# DronePwrCut.net
KiCad netlist of a schematic drawn in EAGLE
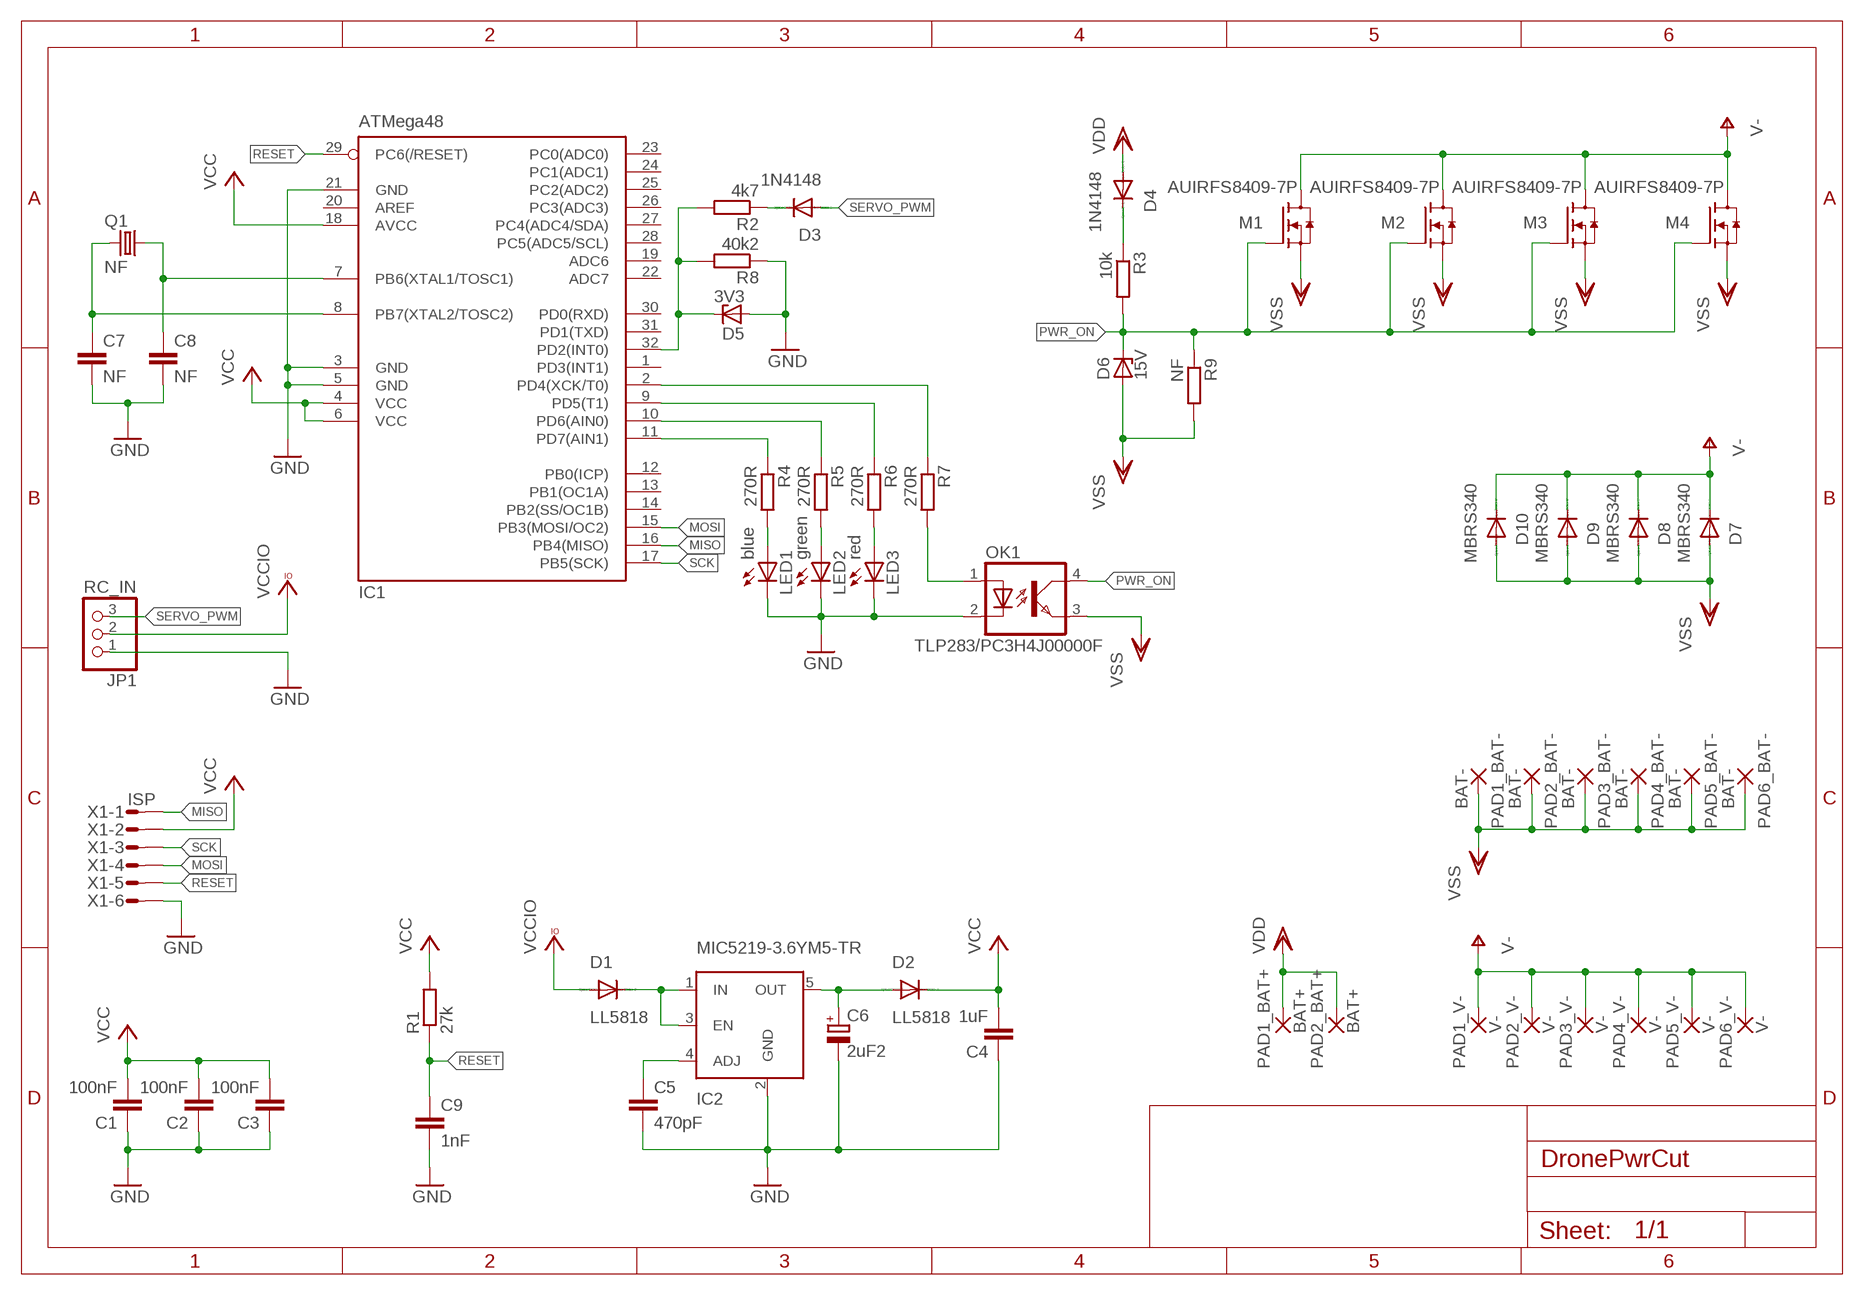
[diagram p0: schematic, sheet 1]

(export (version "E")
  (design (tool "Eeschema 10.0.6"))
  (components
    (comp (ref "C1")
      (value "100nF")
      (footprint "eagle-import:C1206K")
      (libsource (lib "eagle-import") (part "C-EUC1206K"))
    )
    (comp (ref "C2")
      (value "100nF")
      (footprint "eagle-import:C1206K")
      (libsource (lib "eagle-import") (part "C-EUC1206K"))
    )
    (comp (ref "C3")
      (value "100nF")
      (footprint "eagle-import:C1206K")
      (libsource (lib "eagle-import") (part "C-EUC1206K"))
    )
    (comp (ref "C4")
      (value "1uF")
      (footprint "eagle-import:C1206K")
      (libsource (lib "eagle-import") (part "C-EUC1206K"))
    )
    (comp (ref "C5")
      (value "470pF")
      (footprint "eagle-import:C1206K")
      (libsource (lib "eagle-import") (part "C-EUC1206K"))
    )
    (comp (ref "C6")
      (value "2uF2")
      (footprint "eagle-import:SMC_B")
      (libsource (lib "eagle-import") (part "CPOL-EUSMCB"))
    )
    (comp (ref "C7")
      (value "NF")
      (footprint "eagle-import:C1206K")
      (libsource (lib "eagle-import") (part "C-EUC1206K"))
    )
    (comp (ref "C8")
      (value "NF")
      (footprint "eagle-import:C1206K")
      (libsource (lib "eagle-import") (part "C-EUC1206K"))
    )
    (comp (ref "C9")
      (value "1nF")
      (footprint "eagle-import:C1206K")
      (libsource (lib "eagle-import") (part "C-EUC1206K"))
    )
    (comp (ref "D1")
      (value "LL5818")
      (footprint "eagle-import:MELF-MLL41")
      (libsource (lib "eagle-import") (part "DIODE-MELF-MLL41"))
    )
    (comp (ref "D2")
      (value "LL5818")
      (footprint "eagle-import:MELF-MLL41")
      (libsource (lib "eagle-import") (part "DIODE-MELF-MLL41"))
    )
    (comp (ref "D3")
      (value "1N4148")
      (footprint "eagle-import:SOD80C")
      (libsource (lib "eagle-import") (part "DIODE-SOD80C"))
    )
    (comp (ref "D4")
      (value "1N4148")
      (footprint "eagle-import:SOD80C")
      (libsource (lib "eagle-import") (part "DIODE-SOD80C"))
    )
    (comp (ref "D5")
      (value "3V3")
      (footprint "eagle-import:SOD80C")
      (libsource (lib "eagle-import") (part "ZENER-DIODESOD80C"))
    )
    (comp (ref "D6")
      (value "15V")
      (footprint "eagle-import:SOD80C")
      (libsource (lib "eagle-import") (part "ZENER-DIODESOD80C"))
    )
    (comp (ref "D7")
      (value "MBRS340")
      (footprint "eagle-import:SMC")
      (libsource (lib "eagle-import") (part "DIODE-SMC"))
    )
    (comp (ref "D8")
      (value "MBRS340")
      (footprint "eagle-import:SMC")
      (libsource (lib "eagle-import") (part "DIODE-SMC"))
    )
    (comp (ref "D9")
      (value "MBRS340")
      (footprint "eagle-import:SMC")
      (libsource (lib "eagle-import") (part "DIODE-SMC"))
    )
    (comp (ref "D10")
      (value "MBRS340")
      (footprint "eagle-import:SMC")
      (libsource (lib "eagle-import") (part "DIODE-SMC"))
    )
    (comp (ref "IC1")
      (value "ATMega48")
      (footprint "eagle-import:TQFP32-08")
      (fields (field (name "MPN") "ATMEGA8-16AU"))
      (libsource (lib "eagle-import") (part "MEGA8-AI"))
    )
    (comp (ref "IC2")
      (value "MIC5219-3.6YM5-TR")
      (footprint "eagle-import:SOT23-5")
      (fields (field (name "MF") "ALTERA CORPORATION") (field (name "MPN") "MIC5219BM5 TR"))
      (libsource (lib "eagle-import") (part "MIC5219BM5"))
    )
    (comp (ref "JP1")
      (value "RC_IN")
      (footprint "eagle-import:1X03")
      (libsource (lib "eagle-import") (part "PINHD-1X3"))
    )
    (comp (ref "LED1")
      (value "blue")
      (footprint "eagle-import:CHIPLED_1206")
      (libsource (lib "eagle-import") (part "LEDCHIPLED_1206"))
    )
    (comp (ref "LED2")
      (value "green")
      (footprint "eagle-import:CHIPLED_1206")
      (libsource (lib "eagle-import") (part "LEDCHIPLED_1206"))
    )
    (comp (ref "LED3")
      (value "red")
      (footprint "eagle-import:CHIPLED_1206")
      (libsource (lib "eagle-import") (part "LEDCHIPLED_1206"))
    )
    (comp (ref "M1")
      (value "AUIRFS8409-7P")
      (footprint "eagle-import:P-TO263-7-1")
      (libsource (lib "eagle-import") (part "AUIRFS8409-7P"))
    )
    (comp (ref "M2")
      (value "AUIRFS8409-7P")
      (footprint "eagle-import:P-TO263-7-1")
      (libsource (lib "eagle-import") (part "AUIRFS8409-7P"))
    )
    (comp (ref "M3")
      (value "AUIRFS8409-7P")
      (footprint "eagle-import:P-TO263-7-1")
      (libsource (lib "eagle-import") (part "AUIRFS8409-7P"))
    )
    (comp (ref "M4")
      (value "AUIRFS8409-7P")
      (footprint "eagle-import:P-TO263-7-1")
      (libsource (lib "eagle-import") (part "AUIRFS8409-7P"))
    )
    (comp (ref "OK1")
      (value "TLP283/PC3H4J00000F")
      (footprint "eagle-import:MINI-FLAT-4")
      (libsource (lib "eagle-import") (part "TLP283"))
    )
    (comp (ref "PAD1_BAT+")
      (value "BAT+")
      (footprint "eagle-import:1,6_0,8")
      (libsource (lib "eagle-import") (part "1,6/0,8"))
    )
    (comp (ref "PAD1_BAT-")
      (value "BAT-")
      (footprint "eagle-import:1,6_0,8")
      (libsource (lib "eagle-import") (part "1,6/0,8"))
    )
    (comp (ref "PAD1_V-")
      (value "V-")
      (footprint "eagle-import:1,6_0,8")
      (libsource (lib "eagle-import") (part "1,6/0,8"))
    )
    (comp (ref "PAD2_BAT+")
      (value "BAT+")
      (footprint "eagle-import:1,6_0,8")
      (libsource (lib "eagle-import") (part "1,6/0,8"))
    )
    (comp (ref "PAD2_BAT-")
      (value "BAT-")
      (footprint "eagle-import:1,6_0,8")
      (libsource (lib "eagle-import") (part "1,6/0,8"))
    )
    (comp (ref "PAD2_V-")
      (value "V-")
      (footprint "eagle-import:1,6_0,8")
      (libsource (lib "eagle-import") (part "1,6/0,8"))
    )
    (comp (ref "PAD3_BAT-")
      (value "BAT-")
      (footprint "eagle-import:1,6_0,8")
      (libsource (lib "eagle-import") (part "1,6/0,8"))
    )
    (comp (ref "PAD3_V-")
      (value "V-")
      (footprint "eagle-import:1,6_0,8")
      (libsource (lib "eagle-import") (part "1,6/0,8"))
    )
    (comp (ref "PAD4_BAT-")
      (value "BAT-")
      (footprint "eagle-import:1,6_0,8")
      (libsource (lib "eagle-import") (part "1,6/0,8"))
    )
    (comp (ref "PAD4_V-")
      (value "V-")
      (footprint "eagle-import:1,6_0,8")
      (libsource (lib "eagle-import") (part "1,6/0,8"))
    )
    (comp (ref "PAD5_BAT-")
      (value "BAT-")
      (footprint "eagle-import:1,6_0,8")
      (libsource (lib "eagle-import") (part "1,6/0,8"))
    )
    (comp (ref "PAD5_V-")
      (value "V-")
      (footprint "eagle-import:1,6_0,8")
      (libsource (lib "eagle-import") (part "1,6/0,8"))
    )
    (comp (ref "PAD6_BAT-")
      (value "BAT-")
      (footprint "eagle-import:1,6_0,8")
      (libsource (lib "eagle-import") (part "1,6/0,8"))
    )
    (comp (ref "PAD6_V-")
      (value "V-")
      (footprint "eagle-import:1,6_0,8")
      (libsource (lib "eagle-import") (part "1,6/0,8"))
    )
    (comp (ref "Q1")
      (value "NF")
      (footprint "eagle-import:HC49UP")
      (libsource (lib "eagle-import") (part "CRYSTALHC49UP"))
    )
    (comp (ref "R1")
      (value "27k")
      (footprint "eagle-import:R1206")
      (libsource (lib "eagle-import") (part "R-EU_R1206"))
    )
    (comp (ref "R2")
      (value "4k7")
      (footprint "eagle-import:R1206")
      (libsource (lib "eagle-import") (part "R-EU_R1206"))
    )
    (comp (ref "R3")
      (value "10k")
      (footprint "eagle-import:R1206")
      (libsource (lib "eagle-import") (part "R-EU_R1206"))
    )
    (comp (ref "R4")
      (value "270R")
      (footprint "eagle-import:R1206")
      (libsource (lib "eagle-import") (part "R-EU_R1206"))
    )
    (comp (ref "R5")
      (value "270R")
      (footprint "eagle-import:R1206")
      (libsource (lib "eagle-import") (part "R-EU_R1206"))
    )
    (comp (ref "R6")
      (value "270R")
      (footprint "eagle-import:R1206")
      (libsource (lib "eagle-import") (part "R-EU_R1206"))
    )
    (comp (ref "R7")
      (value "270R")
      (footprint "eagle-import:R1206")
      (libsource (lib "eagle-import") (part "R-EU_R1206"))
    )
    (comp (ref "R8")
      (value "40k2")
      (footprint "eagle-import:R1206")
      (libsource (lib "eagle-import") (part "R-EU_R1206"))
    )
    (comp (ref "R9")
      (value "NF")
      (footprint "eagle-import:R1206")
      (libsource (lib "eagle-import") (part "R-EU_R1206"))
    )
    (comp (ref "X1")
      (value "ISP")
      (footprint "eagle-import:MICROMATCH-6")
      (fields (field (name "MPN") "7-215464-6"))
      (libsource (lib "eagle-import") (part "MICROMATCH-6"))
    )
  )
  (nets
    (net (code "1") (name "GND") (class "Default")
      (node (ref "C1") (pin "1") (pinfunction "1_1") (pintype "passive"))
      (node (ref "C2") (pin "1") (pinfunction "1_1") (pintype "passive"))
      (node (ref "C3") (pin "1") (pinfunction "1_1") (pintype "passive"))
      (node (ref "C4") (pin "1") (pinfunction "1_1") (pintype "passive"))
      (node (ref "C5") (pin "2") (pinfunction "2_2") (pintype "passive"))
      (node (ref "C6") (pin "-") (pinfunction "-_-") (pintype "passive"))
      (node (ref "C7") (pin "2") (pinfunction "2_2") (pintype "passive"))
      (node (ref "C8") (pin "2") (pinfunction "2_2") (pintype "passive"))
      (node (ref "C9") (pin "2") (pinfunction "2_2") (pintype "passive"))
      (node (ref "D5") (pin "A") (pinfunction "A_A") (pintype "passive"))
      (node (ref "IC1") (pin "21") (pinfunction "GND_21") (pintype "power_in"))
      (node (ref "IC1") (pin "3") (pinfunction "GND_3") (pintype "power_in"))
      (node (ref "IC1") (pin "5") (pinfunction "GND_5") (pintype "power_in"))
      (node (ref "IC2") (pin "2") (pinfunction "GND_2") (pintype "power_in"))
      (node (ref "JP1") (pin "1") (pinfunction "1_1") (pintype "passive"))
      (node (ref "LED1") (pin "C") (pinfunction "C_C") (pintype "passive"))
      (node (ref "LED2") (pin "C") (pinfunction "C_C") (pintype "passive"))
      (node (ref "LED3") (pin "C") (pinfunction "C_C") (pintype "passive"))
      (node (ref "OK1") (pin "2") (pinfunction "C_2") (pintype "passive"))
      (node (ref "R8") (pin "1") (pinfunction "1_1") (pintype "passive"))
      (node (ref "X1") (pin "6") (pinfunction "S_6") (pintype "passive"))
    )
    (net (code "2") (name "MISO") (class "Default")
      (node (ref "IC1") (pin "16") (pinfunction "PB4(MISO)_16") (pintype "bidirectional"))
      (node (ref "X1") (pin "1") (pinfunction "S_1") (pintype "passive"))
    )
    (net (code "3") (name "MOSI") (class "Default")
      (node (ref "IC1") (pin "15") (pinfunction "PB3(MOSI/OC2)_15") (pintype "bidirectional"))
      (node (ref "X1") (pin "4") (pinfunction "S_4") (pintype "passive"))
    )
    (net (code "4") (name "Net-(D3-PadC)") (class "Default")
      (node (ref "D3") (pin "C") (pinfunction "C_C") (pintype "passive"))
      (node (ref "R2") (pin "1") (pinfunction "1_1") (pintype "passive"))
    )
    (net (code "5") (name "Net-(D4-PadC)") (class "Default")
      (node (ref "D4") (pin "C") (pinfunction "C_C") (pintype "passive"))
      (node (ref "R3") (pin "1") (pinfunction "1_1") (pintype "passive"))
    )
    (net (code "6") (name "Net-(IC1-PB6(XTAL1{slash}TOSC1))") (class "Default")
      (node (ref "C8") (pin "1") (pinfunction "1_1") (pintype "passive"))
      (node (ref "IC1") (pin "7") (pinfunction "PB6(XTAL1/TOSC1)_7") (pintype "bidirectional"))
      (node (ref "Q1") (pin "1") (pinfunction "1_1") (pintype "passive"))
    )
    (net (code "7") (name "Net-(IC1-PB7(XTAL2{slash}TOSC2))") (class "Default")
      (node (ref "C7") (pin "1") (pinfunction "1_1") (pintype "passive"))
      (node (ref "IC1") (pin "8") (pinfunction "PB7(XTAL2/TOSC2)_8") (pintype "bidirectional"))
      (node (ref "Q1") (pin "2") (pinfunction "2_2") (pintype "passive"))
    )
    (net (code "8") (name "Net-(IC1-PD2(INT0))") (class "Default")
      (node (ref "D5") (pin "C") (pinfunction "C_C") (pintype "passive"))
      (node (ref "IC1") (pin "32") (pinfunction "PD2(INT0)_32") (pintype "bidirectional"))
      (node (ref "R2") (pin "2") (pinfunction "2_2") (pintype "passive"))
      (node (ref "R8") (pin "2") (pinfunction "2_2") (pintype "passive"))
    )
    (net (code "9") (name "Net-(IC1-PD4(XCK{slash}T0))") (class "Default")
      (node (ref "IC1") (pin "2") (pinfunction "PD4(XCK/T0)_2") (pintype "bidirectional"))
      (node (ref "R7") (pin "1") (pinfunction "1_1") (pintype "passive"))
    )
    (net (code "10") (name "Net-(IC1-PD5(T1))") (class "Default")
      (node (ref "IC1") (pin "9") (pinfunction "PD5(T1)_9") (pintype "bidirectional"))
      (node (ref "R6") (pin "1") (pinfunction "1_1") (pintype "passive"))
    )
    (net (code "11") (name "Net-(IC1-PD6(AIN0))") (class "Default")
      (node (ref "IC1") (pin "10") (pinfunction "PD6(AIN0)_10") (pintype "bidirectional"))
      (node (ref "R5") (pin "1") (pinfunction "1_1") (pintype "passive"))
    )
    (net (code "12") (name "Net-(IC1-PD7(AIN1))") (class "Default")
      (node (ref "IC1") (pin "11") (pinfunction "PD7(AIN1)_11") (pintype "bidirectional"))
      (node (ref "R4") (pin "1") (pinfunction "1_1") (pintype "passive"))
    )
    (net (code "13") (name "Net-(IC2-ADJ)") (class "Default")
      (node (ref "C5") (pin "1") (pinfunction "1_1") (pintype "passive"))
      (node (ref "IC2") (pin "4") (pinfunction "ADJ_4") (pintype "passive"))
    )
    (net (code "14") (name "Net-(IC2-EN)") (class "Default")
      (node (ref "D1") (pin "C") (pinfunction "C_C") (pintype "passive"))
      (node (ref "IC2") (pin "1") (pinfunction "IN_1") (pintype "input"))
      (node (ref "IC2") (pin "3") (pinfunction "EN_3") (pintype "input"))
    )
    (net (code "15") (name "Net-(IC2-OUT)") (class "Default")
      (node (ref "C6") (pin "+") (pinfunction "+_+") (pintype "passive"))
      (node (ref "D2") (pin "A") (pinfunction "A_A") (pintype "passive"))
      (node (ref "IC2") (pin "5") (pinfunction "OUT_5") (pintype "passive"))
    )
    (net (code "16") (name "Net-(LED1-PadA)") (class "Default")
      (node (ref "LED1") (pin "A") (pinfunction "A_A") (pintype "passive"))
      (node (ref "R4") (pin "2") (pinfunction "2_2") (pintype "passive"))
    )
    (net (code "17") (name "Net-(LED2-PadA)") (class "Default")
      (node (ref "LED2") (pin "A") (pinfunction "A_A") (pintype "passive"))
      (node (ref "R5") (pin "2") (pinfunction "2_2") (pintype "passive"))
    )
    (net (code "18") (name "Net-(LED3-PadA)") (class "Default")
      (node (ref "LED3") (pin "A") (pinfunction "A_A") (pintype "passive"))
      (node (ref "R6") (pin "2") (pinfunction "2_2") (pintype "passive"))
    )
    (net (code "19") (name "Net-(OK1-A)") (class "Default")
      (node (ref "OK1") (pin "1") (pinfunction "A_1") (pintype "passive"))
      (node (ref "R7") (pin "2") (pinfunction "2_2") (pintype "passive"))
    )
    (net (code "20") (name "PWR_ON") (class "Default")
      (node (ref "D6") (pin "C") (pinfunction "C_C") (pintype "passive"))
      (node (ref "M1") (pin "1") (pinfunction "G_1") (pintype "passive"))
      (node (ref "M2") (pin "1") (pinfunction "G_1") (pintype "passive"))
      (node (ref "M3") (pin "1") (pinfunction "G_1") (pintype "passive"))
      (node (ref "M4") (pin "1") (pinfunction "G_1") (pintype "passive"))
      (node (ref "OK1") (pin "4") (pinfunction "COL_4") (pintype "passive"))
      (node (ref "R3") (pin "2") (pinfunction "2_2") (pintype "passive"))
      (node (ref "R9") (pin "1") (pinfunction "1_1") (pintype "passive"))
    )
    (net (code "21") (name "RESET") (class "Default")
      (node (ref "C9") (pin "1") (pinfunction "1_1") (pintype "passive"))
      (node (ref "IC1") (pin "29") (pinfunction "PC6(/RESET)_29") (pintype "bidirectional"))
      (node (ref "R1") (pin "1") (pinfunction "1_1") (pintype "passive"))
      (node (ref "X1") (pin "5") (pinfunction "S_5") (pintype "passive"))
    )
    (net (code "22") (name "SCK") (class "Default")
      (node (ref "IC1") (pin "17") (pinfunction "PB5(SCK)_17") (pintype "bidirectional"))
      (node (ref "X1") (pin "3") (pinfunction "S_3") (pintype "passive"))
    )
    (net (code "23") (name "SERVO_PWM") (class "Default")
      (node (ref "D3") (pin "A") (pinfunction "A_A") (pintype "passive"))
      (node (ref "JP1") (pin "3") (pinfunction "3_3") (pintype "passive"))
    )
    (net (code "24") (name "V-") (class "Default")
      (node (ref "D10") (pin "C") (pinfunction "C_C") (pintype "passive"))
      (node (ref "D7") (pin "C") (pinfunction "C_C") (pintype "passive"))
      (node (ref "D8") (pin "C") (pinfunction "C_C") (pintype "passive"))
      (node (ref "D9") (pin "C") (pinfunction "C_C") (pintype "passive"))
      (node (ref "M1") (pin "7") (pinfunction "D_7") (pintype "passive"))
      (node (ref "M2") (pin "7") (pinfunction "D_7") (pintype "passive"))
      (node (ref "M3") (pin "7") (pinfunction "D_7") (pintype "passive"))
      (node (ref "M4") (pin "7") (pinfunction "D_7") (pintype "passive"))
      (node (ref "PAD1_V-") (pin "1") (pinfunction "P_1") (pintype "passive"))
      (node (ref "PAD2_V-") (pin "1") (pinfunction "P_1") (pintype "passive"))
      (node (ref "PAD3_V-") (pin "1") (pinfunction "P_1") (pintype "passive"))
      (node (ref "PAD4_V-") (pin "1") (pinfunction "P_1") (pintype "passive"))
      (node (ref "PAD5_V-") (pin "1") (pinfunction "P_1") (pintype "passive"))
      (node (ref "PAD6_V-") (pin "1") (pinfunction "P_1") (pintype "passive"))
    )
    (net (code "25") (name "VCC") (class "Default")
      (node (ref "C1") (pin "2") (pinfunction "2_2") (pintype "passive"))
      (node (ref "C2") (pin "2") (pinfunction "2_2") (pintype "passive"))
      (node (ref "C3") (pin "2") (pinfunction "2_2") (pintype "passive"))
      (node (ref "C4") (pin "2") (pinfunction "2_2") (pintype "passive"))
      (node (ref "D2") (pin "C") (pinfunction "C_C") (pintype "passive"))
      (node (ref "IC1") (pin "18") (pinfunction "AVCC_18") (pintype "power_in"))
      (node (ref "IC1") (pin "4") (pinfunction "VCC_4") (pintype "power_in"))
      (node (ref "IC1") (pin "6") (pinfunction "VCC_6") (pintype "power_in"))
      (node (ref "R1") (pin "2") (pinfunction "2_2") (pintype "passive"))
      (node (ref "X1") (pin "2") (pinfunction "S_2") (pintype "passive"))
    )
    (net (code "26") (name "VCCIO") (class "Default")
      (node (ref "D1") (pin "A") (pinfunction "A_A") (pintype "passive"))
      (node (ref "JP1") (pin "2") (pinfunction "2_2") (pintype "passive"))
    )
    (net (code "27") (name "VDD") (class "Default")
      (node (ref "D4") (pin "A") (pinfunction "A_A") (pintype "passive"))
      (node (ref "PAD1_BAT+") (pin "1") (pinfunction "P_1") (pintype "passive"))
      (node (ref "PAD2_BAT+") (pin "1") (pinfunction "P_1") (pintype "passive"))
    )
    (net (code "28") (name "VSS") (class "Default")
      (node (ref "D10") (pin "A") (pinfunction "A_A") (pintype "passive"))
      (node (ref "D6") (pin "A") (pinfunction "A_A") (pintype "passive"))
      (node (ref "D7") (pin "A") (pinfunction "A_A") (pintype "passive"))
      (node (ref "D8") (pin "A") (pinfunction "A_A") (pintype "passive"))
      (node (ref "D9") (pin "A") (pinfunction "A_A") (pintype "passive"))
      (node (ref "M1") (pin "2") (pinfunction "S_2") (pintype "passive"))
      (node (ref "M1") (pin "3") (pinfunction "S_3") (pintype "passive"))
      (node (ref "M1") (pin "4") (pinfunction "S_4") (pintype "passive"))
      (node (ref "M1") (pin "5") (pinfunction "S_5") (pintype "passive"))
      (node (ref "M1") (pin "6") (pinfunction "S_6") (pintype "passive"))
      (node (ref "M2") (pin "2") (pinfunction "S_2") (pintype "passive"))
      (node (ref "M2") (pin "3") (pinfunction "S_3") (pintype "passive"))
      (node (ref "M2") (pin "4") (pinfunction "S_4") (pintype "passive"))
      (node (ref "M2") (pin "5") (pinfunction "S_5") (pintype "passive"))
      (node (ref "M2") (pin "6") (pinfunction "S_6") (pintype "passive"))
      (node (ref "M3") (pin "2") (pinfunction "S_2") (pintype "passive"))
      (node (ref "M3") (pin "3") (pinfunction "S_3") (pintype "passive"))
      (node (ref "M3") (pin "4") (pinfunction "S_4") (pintype "passive"))
      (node (ref "M3") (pin "5") (pinfunction "S_5") (pintype "passive"))
      (node (ref "M3") (pin "6") (pinfunction "S_6") (pintype "passive"))
      (node (ref "M4") (pin "2") (pinfunction "S_2") (pintype "passive"))
      (node (ref "M4") (pin "3") (pinfunction "S_3") (pintype "passive"))
      (node (ref "M4") (pin "4") (pinfunction "S_4") (pintype "passive"))
      (node (ref "M4") (pin "5") (pinfunction "S_5") (pintype "passive"))
      (node (ref "M4") (pin "6") (pinfunction "S_6") (pintype "passive"))
      (node (ref "OK1") (pin "3") (pinfunction "EMIT_3") (pintype "passive"))
      (node (ref "PAD1_BAT-") (pin "1") (pinfunction "P_1") (pintype "passive"))
      (node (ref "PAD2_BAT-") (pin "1") (pinfunction "P_1") (pintype "passive"))
      (node (ref "PAD3_BAT-") (pin "1") (pinfunction "P_1") (pintype "passive"))
      (node (ref "PAD4_BAT-") (pin "1") (pinfunction "P_1") (pintype "passive"))
      (node (ref "PAD5_BAT-") (pin "1") (pinfunction "P_1") (pintype "passive"))
      (node (ref "PAD6_BAT-") (pin "1") (pinfunction "P_1") (pintype "passive"))
      (node (ref "R9") (pin "2") (pinfunction "2_2") (pintype "passive"))
    )
    (net (code "29") (name "unconnected-(IC1-ADC6-Pad19)") (class "Default")
      (node (ref "IC1") (pin "19") (pinfunction "ADC6_19") (pintype "bidirectional"))
    )
    (net (code "30") (name "unconnected-(IC1-ADC7-Pad22)") (class "Default")
      (node (ref "IC1") (pin "22") (pinfunction "ADC7_22") (pintype "bidirectional"))
    )
    (net (code "31") (name "unconnected-(IC1-AREF-Pad20)") (class "Default")
      (node (ref "IC1") (pin "20") (pinfunction "AREF_20") (pintype "passive"))
    )
    (net (code "32") (name "unconnected-(IC1-PB0(ICP)-Pad12)") (class "Default")
      (node (ref "IC1") (pin "12") (pinfunction "PB0(ICP)_12") (pintype "bidirectional"))
    )
    (net (code "33") (name "unconnected-(IC1-PB1(OC1A)-Pad13)") (class "Default")
      (node (ref "IC1") (pin "13") (pinfunction "PB1(OC1A)_13") (pintype "bidirectional"))
    )
    (net (code "34") (name "unconnected-(IC1-PB2(SS{slash}OC1B)-Pad14)") (class "Default")
      (node (ref "IC1") (pin "14") (pinfunction "PB2(SS/OC1B)_14") (pintype "bidirectional"))
    )
    (net (code "35") (name "unconnected-(IC1-PC0(ADC0)-Pad23)") (class "Default")
      (node (ref "IC1") (pin "23") (pinfunction "PC0(ADC0)_23") (pintype "bidirectional"))
    )
    (net (code "36") (name "unconnected-(IC1-PC1(ADC1)-Pad24)") (class "Default")
      (node (ref "IC1") (pin "24") (pinfunction "PC1(ADC1)_24") (pintype "bidirectional"))
    )
    (net (code "37") (name "unconnected-(IC1-PC2(ADC2)-Pad25)") (class "Default")
      (node (ref "IC1") (pin "25") (pinfunction "PC2(ADC2)_25") (pintype "bidirectional"))
    )
    (net (code "38") (name "unconnected-(IC1-PC3(ADC3)-Pad26)") (class "Default")
      (node (ref "IC1") (pin "26") (pinfunction "PC3(ADC3)_26") (pintype "bidirectional"))
    )
    (net (code "39") (name "unconnected-(IC1-PC4(ADC4{slash}SDA)-Pad27)") (class "Default")
      (node (ref "IC1") (pin "27") (pinfunction "PC4(ADC4/SDA)_27") (pintype "bidirectional"))
    )
    (net (code "40") (name "unconnected-(IC1-PC5(ADC5{slash}SCL)-Pad28)") (class "Default")
      (node (ref "IC1") (pin "28") (pinfunction "PC5(ADC5/SCL)_28") (pintype "bidirectional"))
    )
    (net (code "41") (name "unconnected-(IC1-PD0(RXD)-Pad30)") (class "Default")
      (node (ref "IC1") (pin "30") (pinfunction "PD0(RXD)_30") (pintype "bidirectional"))
    )
    (net (code "42") (name "unconnected-(IC1-PD1(TXD)-Pad31)") (class "Default")
      (node (ref "IC1") (pin "31") (pinfunction "PD1(TXD)_31") (pintype "bidirectional"))
    )
    (net (code "43") (name "unconnected-(IC1-PD3(INT1)-Pad1)") (class "Default")
      (node (ref "IC1") (pin "1") (pinfunction "PD3(INT1)_1") (pintype "bidirectional"))
    )
  )
)
